# Mergen_Ground_Station_V2_0.net
KiCad netlist of a schematic drawn in EAGLE
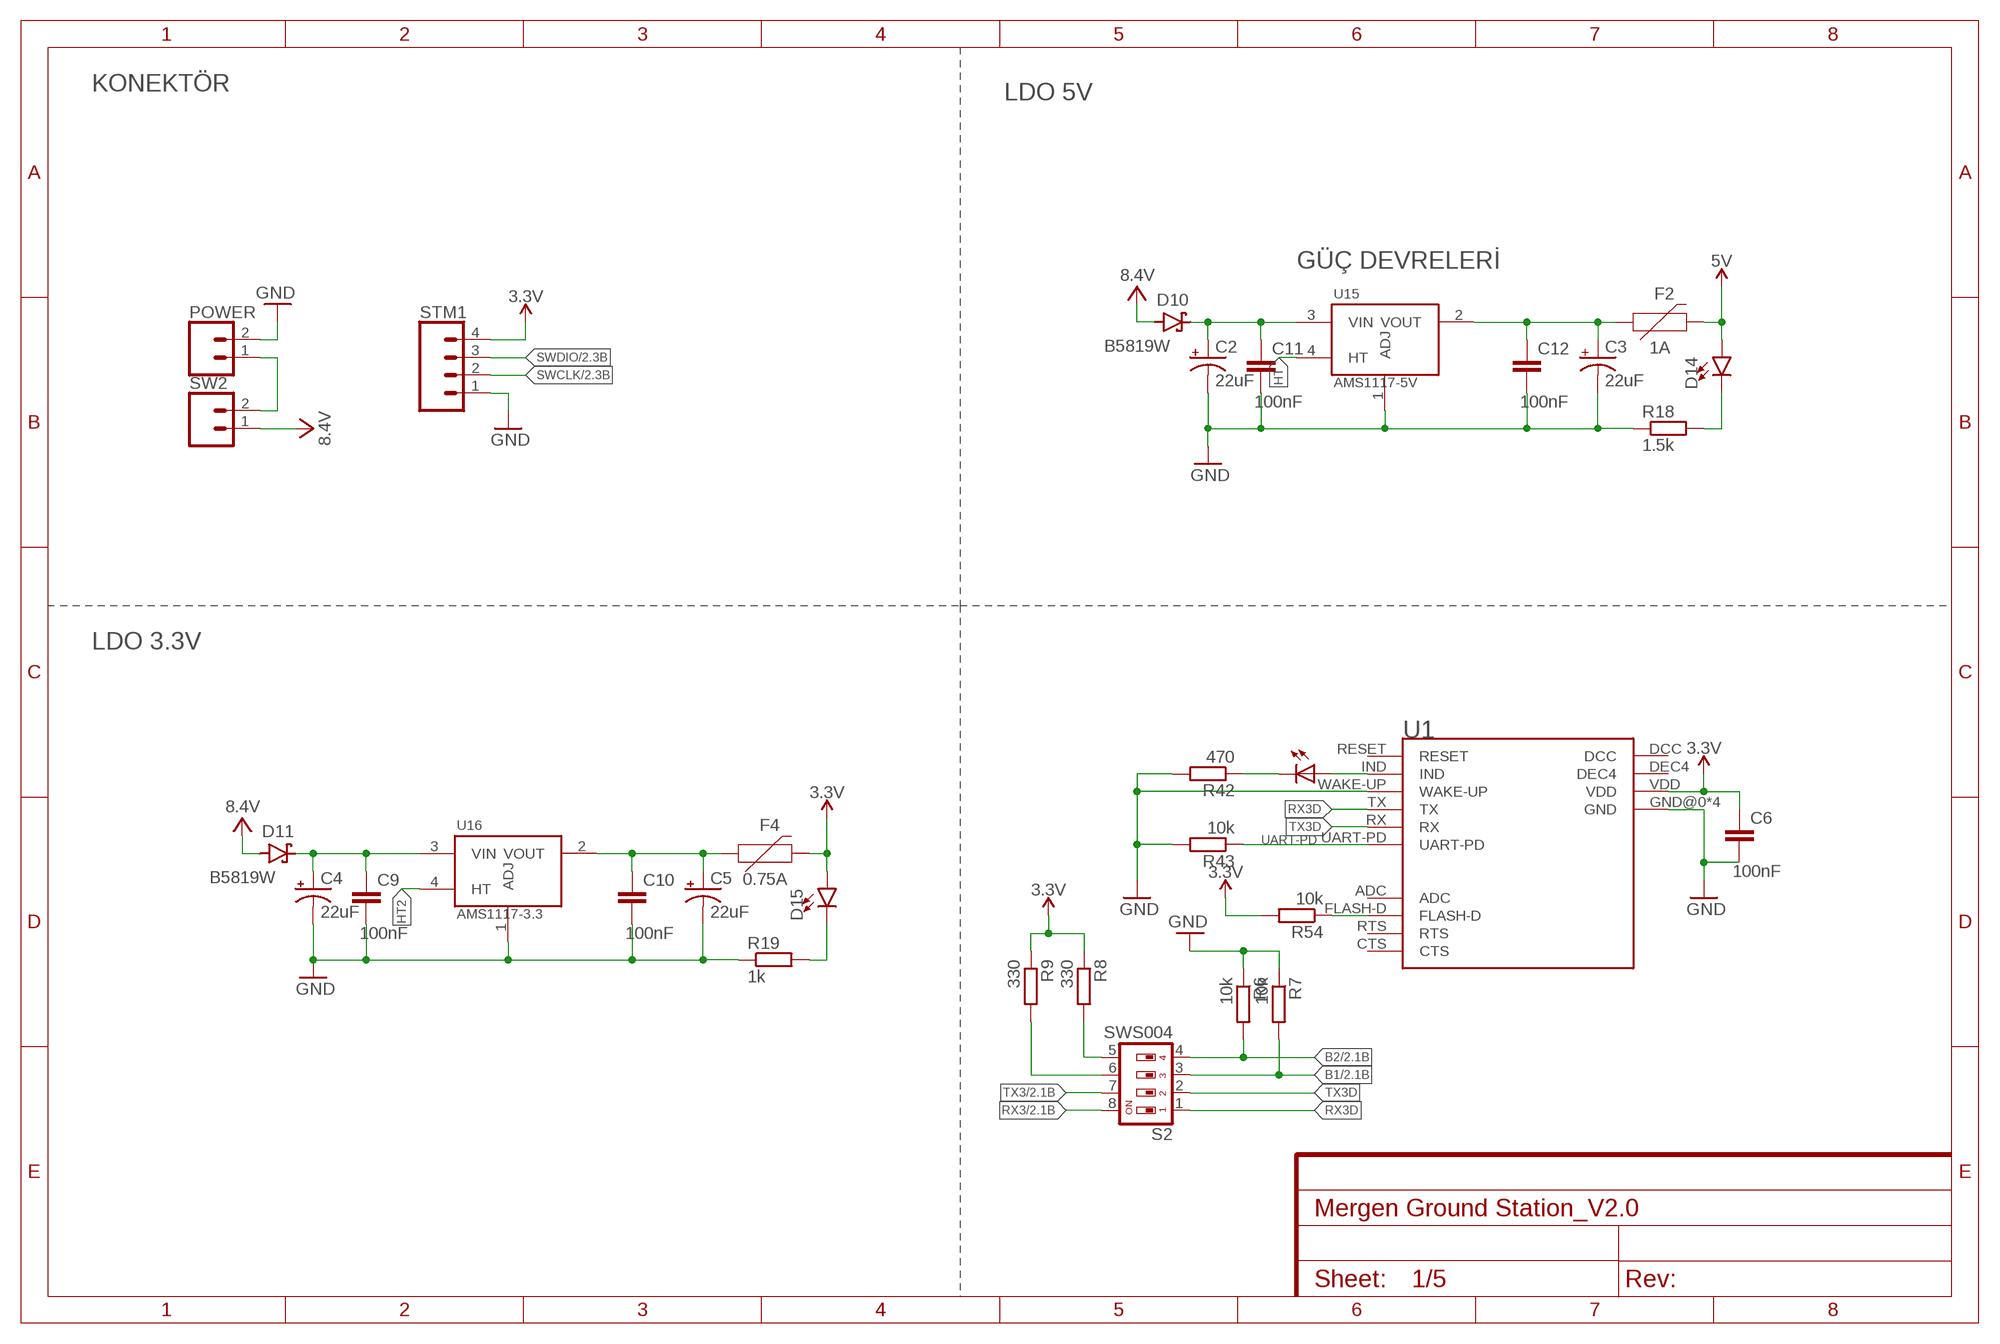
[diagram p0: schematic, sheet 1]
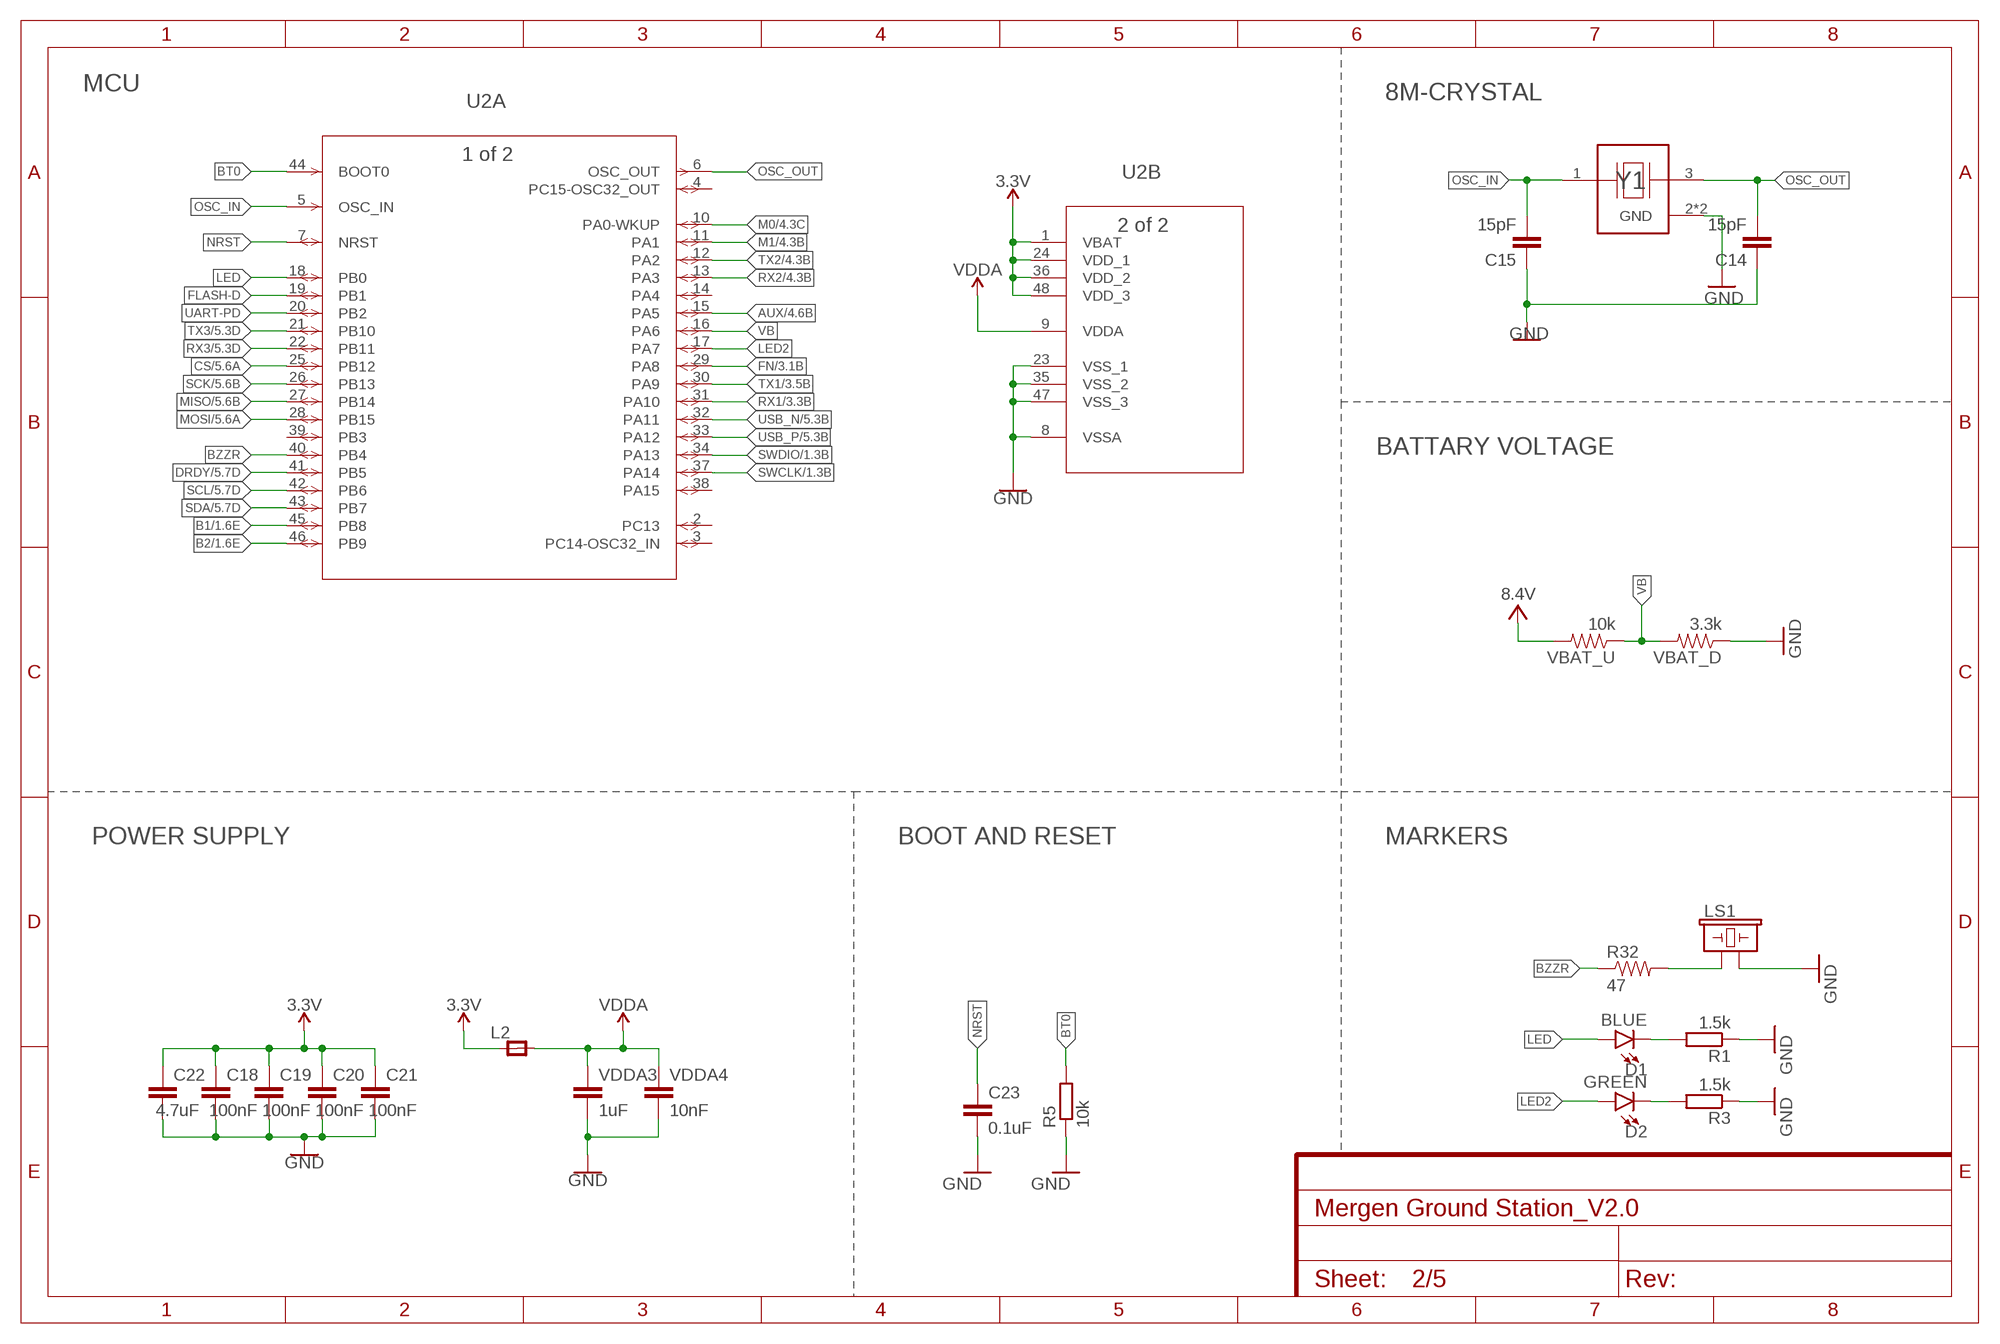
[diagram p1: schematic, sheet 2]
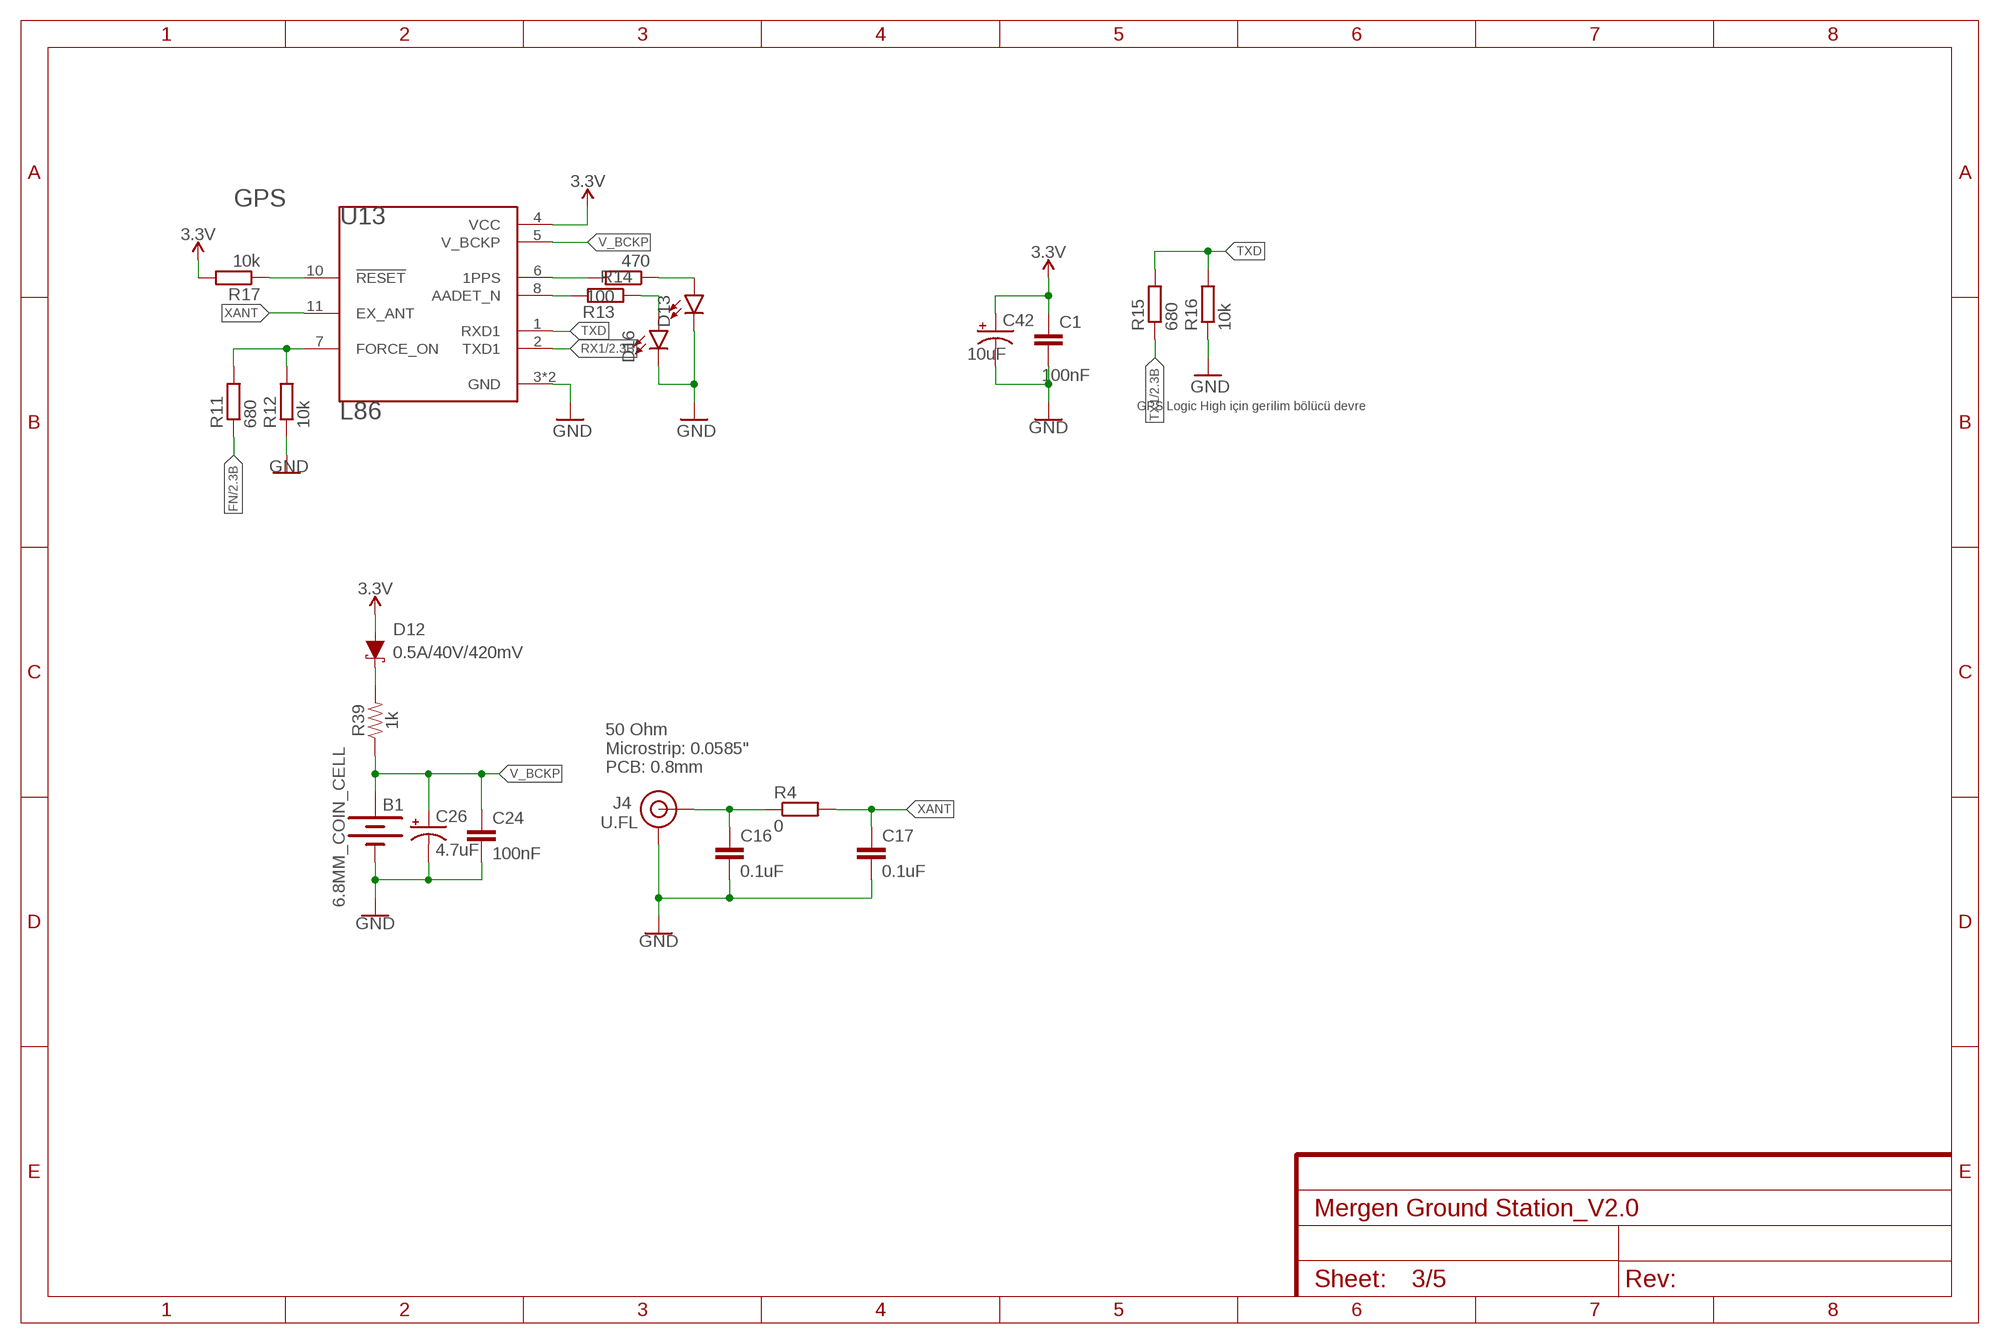
[diagram p2: schematic, sheet 3]
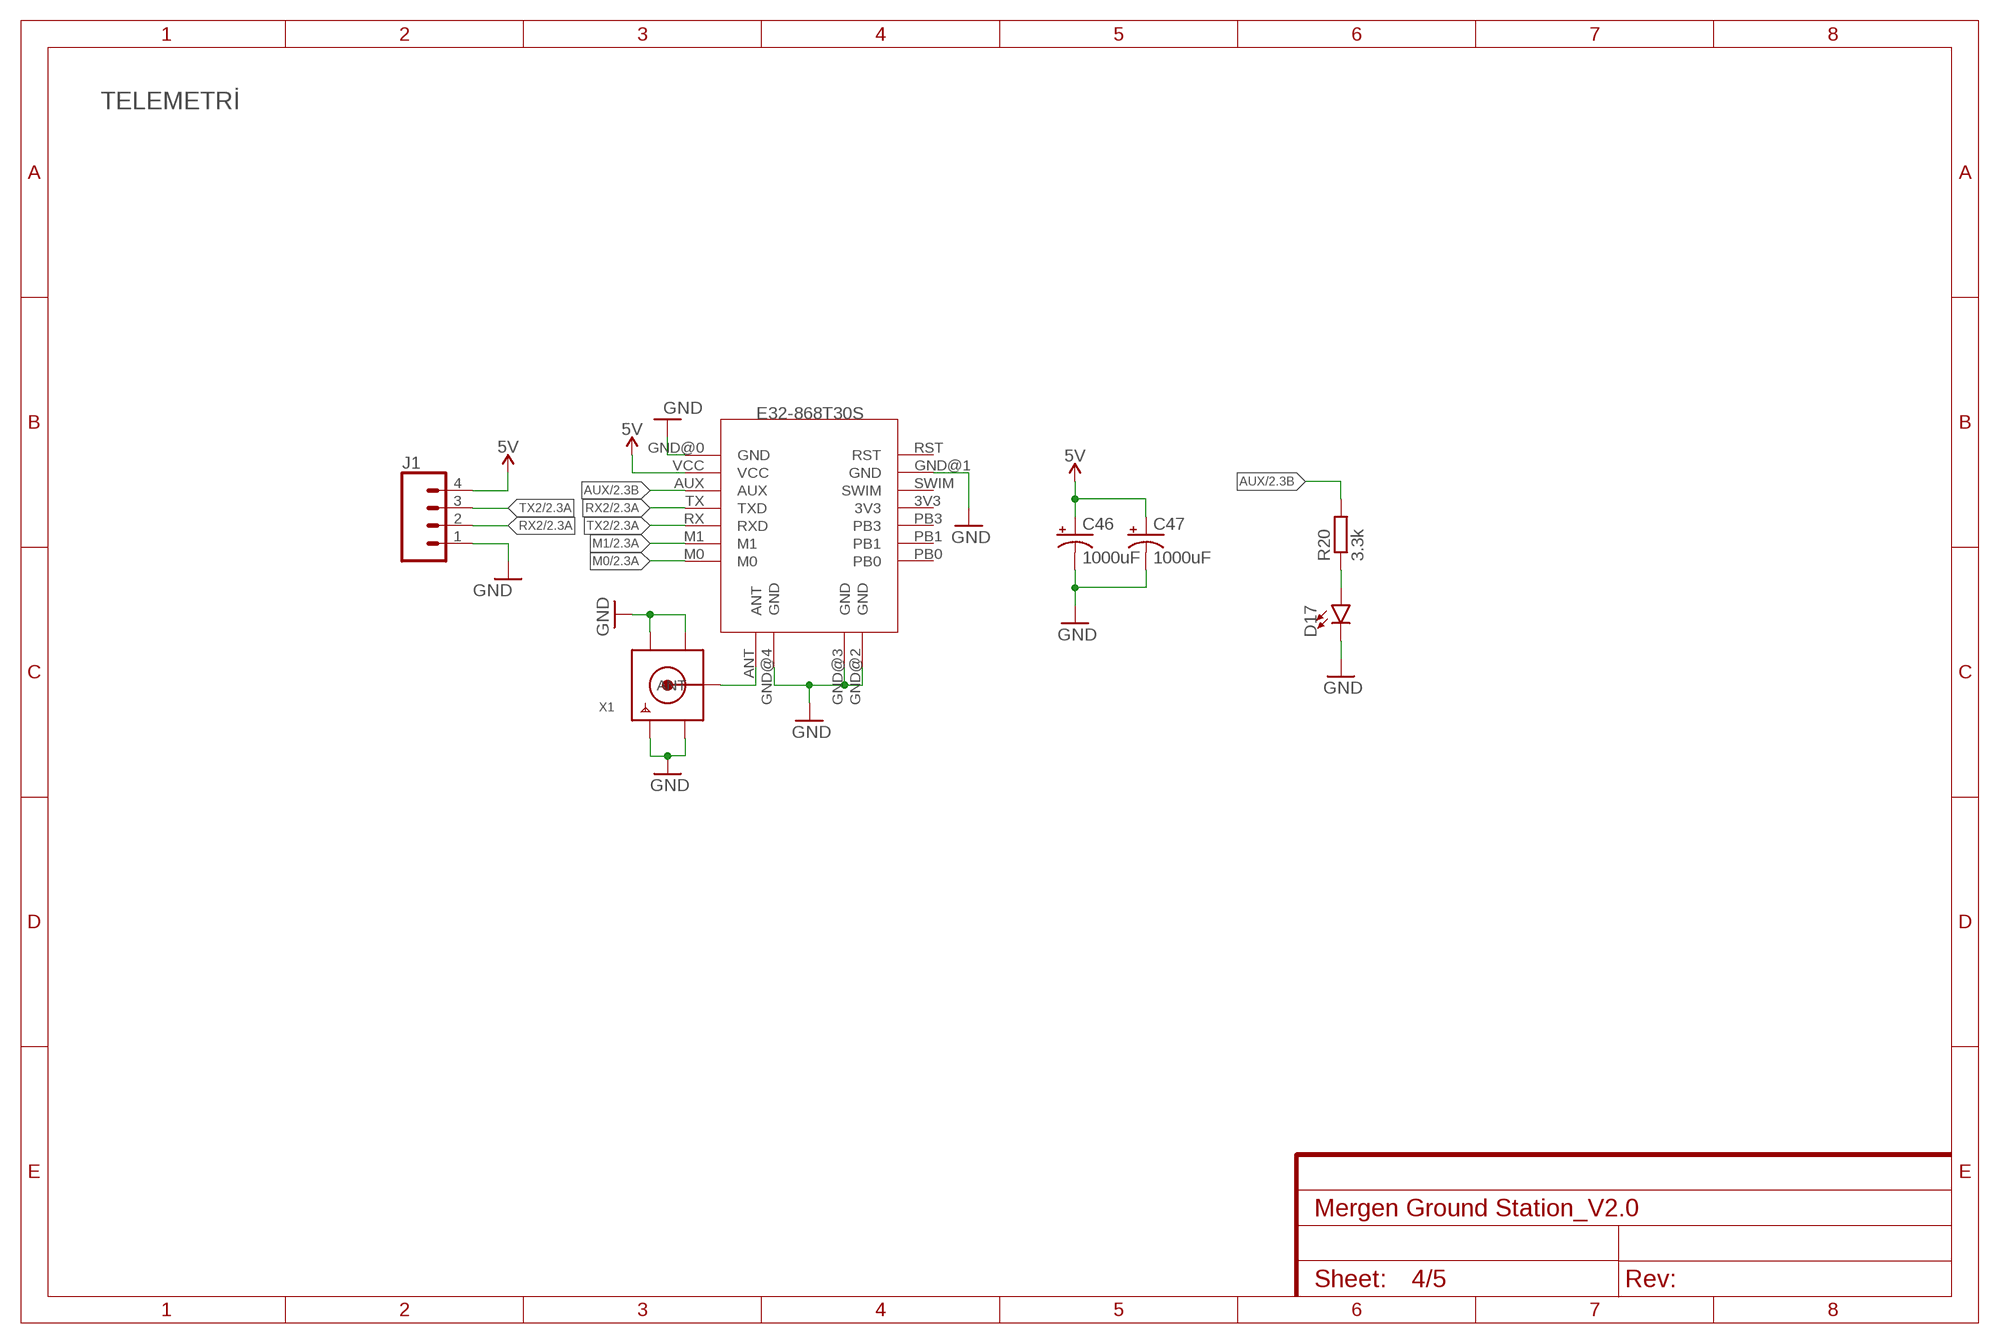
[diagram p3: schematic, sheet 4]
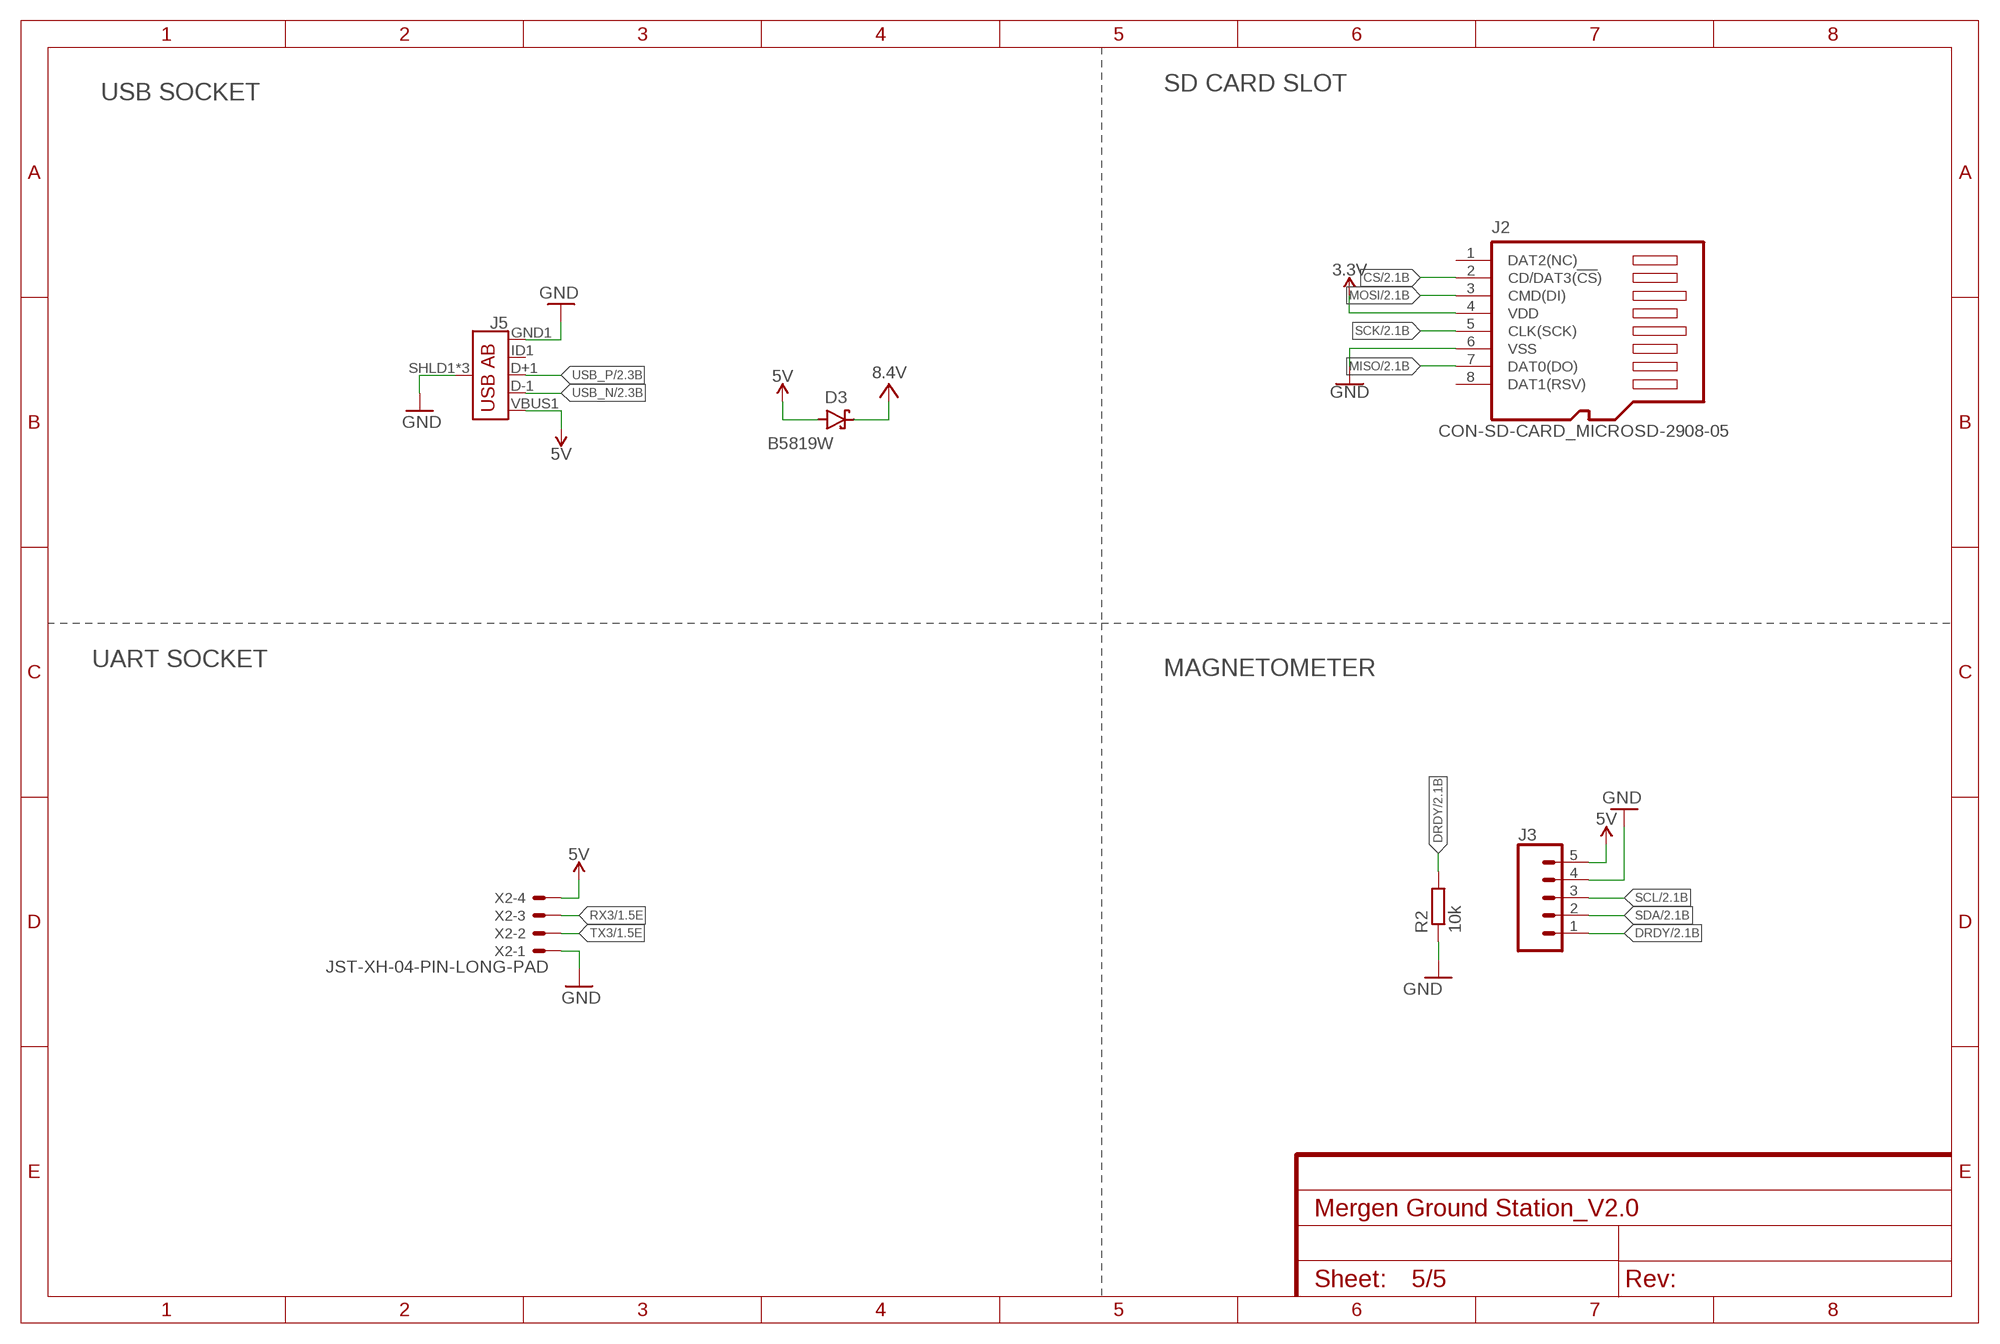
[diagram p4: schematic, sheet 5]

(export (version "E")
  (design (tool "Eeschema 10.0.6"))
  (components
    (comp (ref "B1")
      (value "6.8MM_COIN_CELL")
      (footprint "eagle-import:BATTCON-6.8MM")
      (libsource (lib "eagle-import") (part "BATTERY-6.8MM_SMD"))
    )
    (comp (ref "C1")
      (value "100nF")
      (footprint "eagle-import:C0603")
      (libsource (lib "eagle-import") (part "C-EUC0603"))
    )
    (comp (ref "C16")
      (value "0.1uF")
      (footprint "eagle-import:C0603")
      (libsource (lib "eagle-import") (part "C-EUC0603"))
    )
    (comp (ref "C17")
      (value "0.1uF")
      (footprint "eagle-import:C0603")
      (libsource (lib "eagle-import") (part "C-EUC0603"))
    )
    (comp (ref "C24")
      (value "100nF")
      (footprint "eagle-import:C0603")
      (libsource (lib "eagle-import") (part "C-EUC0603"))
    )
    (comp (ref "C26")
      (value "4.7uF")
      (footprint "eagle-import:A_3216-18R")
      (libsource (lib "eagle-import") (part "rcl_334_CPOL-USA/3216-18R"))
    )
    (comp (ref "C42")
      (value "10uF")
      (footprint "eagle-import:EIA3216")
      (libsource (lib "eagle-import") (part "10UF-POLAR-EIA3216-16V-10%(TANT)"))
    )
    (comp (ref "D12")
      (value "0.5A/40V/420mV")
      (footprint "eagle-import:SOD-323")
      (libsource (lib "eagle-import") (part "DIODE-SCHOTTKY-PMEG4005EJ"))
    )
    (comp (ref "D13")
      (value "LED0603")
      (footprint "eagle-import:LED-0603")
      (libsource (lib "eagle-import") (part "LED0603"))
    )
    (comp (ref "D16")
      (value "LED0603")
      (footprint "eagle-import:LED-0603")
      (libsource (lib "eagle-import") (part "LED0603"))
    )
    (comp (ref "J4")
      (value "U.FL")
      (footprint "eagle-import:U.FL")
      (libsource (lib "eagle-import") (part "U.FL2PIN"))
    )
    (comp (ref "R4")
      (value "0")
      (footprint "eagle-import:R0603")
      (libsource (lib "eagle-import") (part "rcl_334_R-EU_R0603"))
    )
    (comp (ref "R11")
      (value "680")
      (footprint "eagle-import:R0603")
      (libsource (lib "eagle-import") (part "rcl_334_R-EU_R0603"))
    )
    (comp (ref "R12")
      (value "10k")
      (footprint "eagle-import:R0603")
      (libsource (lib "eagle-import") (part "rcl_334_R-EU_R0603"))
    )
    (comp (ref "R13")
      (value "100")
      (footprint "eagle-import:R0603")
      (libsource (lib "eagle-import") (part "rcl_334_R-EU_R0603"))
    )
    (comp (ref "R14")
      (value "470")
      (footprint "eagle-import:R0603")
      (libsource (lib "eagle-import") (part "rcl_334_R-EU_R0603"))
    )
    (comp (ref "R15")
      (value "680")
      (footprint "eagle-import:R0603")
      (libsource (lib "eagle-import") (part "rcl_334_R-EU_R0603"))
    )
    (comp (ref "R16")
      (value "10k")
      (footprint "eagle-import:R0603")
      (libsource (lib "eagle-import") (part "rcl_334_R-EU_R0603"))
    )
    (comp (ref "R17")
      (value "10k")
      (footprint "eagle-import:R0603")
      (libsource (lib "eagle-import") (part "rcl_334_R-EU_R0603"))
    )
    (comp (ref "R39")
      (value "1k")
      (footprint "eagle-import:0603")
      (libsource (lib "eagle-import") (part "1KOHM-0603-1/10W-1%"))
    )
    (comp (ref "U13")
      (value "L86")
      (footprint "eagle-import:XCVR_L86")
      (fields (field (name "MF") "Quectel"))
      (libsource (lib "eagle-import") (part "L86"))
    )
    (comp (ref "C2")
      (value "22uF")
      (footprint "eagle-import:CT3528")
      (libsource (lib "eagle-import") (part "rcl_334_CPOL-USCT3528"))
    )
    (comp (ref "C3")
      (value "22uF")
      (footprint "eagle-import:CT3528")
      (libsource (lib "eagle-import") (part "rcl_334_CPOL-USCT3528"))
    )
    (comp (ref "C4")
      (value "22uF")
      (footprint "eagle-import:CT3528")
      (libsource (lib "eagle-import") (part "rcl_334_CPOL-USCT3528"))
    )
    (comp (ref "C5")
      (value "22uF")
      (footprint "eagle-import:CT3528")
      (libsource (lib "eagle-import") (part "rcl_334_CPOL-USCT3528"))
    )
    (comp (ref "C6")
      (value "100nF")
      (footprint "eagle-import:C0603")
      (libsource (lib "eagle-import") (part "C-EUC0603"))
    )
    (comp (ref "C9")
      (value "100nF")
      (footprint "eagle-import:C0603")
      (libsource (lib "eagle-import") (part "C-EUC0603"))
    )
    (comp (ref "C10")
      (value "100nF")
      (footprint "eagle-import:C0603")
      (libsource (lib "eagle-import") (part "C-EUC0603"))
    )
    (comp (ref "C11")
      (value "100nF")
      (footprint "eagle-import:C0603")
      (libsource (lib "eagle-import") (part "C-EUC0603"))
    )
    (comp (ref "C12")
      (value "100nF")
      (footprint "eagle-import:C0603")
      (libsource (lib "eagle-import") (part "C-EUC0603"))
    )
    (comp (ref "D10")
      (value "B5819W")
      (footprint "eagle-import:SODFL3718X115")
      (fields (field (name "MANUFACTURER") "ON Semiconductor") (field (name "MPN") "MBR0520LT1G"))
      (libsource (lib "eagle-import") (part "SCHOTTKY_DO-219MBR0520LT1G"))
    )
    (comp (ref "D11")
      (value "B5819W")
      (footprint "eagle-import:SODFL3718X115")
      (fields (field (name "MANUFACTURER") "ON Semiconductor") (field (name "MPN") "MBR0520LT1G"))
      (libsource (lib "eagle-import") (part "SCHOTTKY_DO-219MBR0520LT1G"))
    )
    (comp (ref "D14")
      (value "LED0603")
      (footprint "eagle-import:LED-0603")
      (libsource (lib "eagle-import") (part "LED0603"))
    )
    (comp (ref "D15")
      (value "LED0603")
      (footprint "eagle-import:LED-0603")
      (libsource (lib "eagle-import") (part "LED0603"))
    )
    (comp (ref "DRM3")
      (value "kirmizi")
      (footprint "eagle-import:CHIP-LED0805")
      (libsource (lib "eagle-import") (part "LEDCHIP-LED0805"))
    )
    (comp (ref "F2")
      (value "1A")
      (footprint "eagle-import:1206")
      (libsource (lib "eagle-import") (part "PPTC_HALF-AMP"))
    )
    (comp (ref "F4")
      (value "0.75A")
      (footprint "eagle-import:1206")
      (libsource (lib "eagle-import") (part "PPTC_HALF-AMP"))
    )
    (comp (ref "POWER")
      (value "CONN_023.5MM-NO_SILK")
      (footprint "eagle-import:SCREWTERMINAL-3.5MM-2-NS")
      (libsource (lib "eagle-import") (part "CONN_023.5MM-NO_SILK"))
    )
    (comp (ref "R6")
      (value "10k")
      (footprint "eagle-import:R0603")
      (libsource (lib "eagle-import") (part "R-EU_R0603"))
    )
    (comp (ref "R7")
      (value "10k")
      (footprint "eagle-import:R0603")
      (libsource (lib "eagle-import") (part "R-EU_R0603"))
    )
    (comp (ref "R8")
      (value "330")
      (footprint "eagle-import:R0603")
      (libsource (lib "eagle-import") (part "R-EU_R0603"))
    )
    (comp (ref "R9")
      (value "330")
      (footprint "eagle-import:R0603")
      (libsource (lib "eagle-import") (part "R-EU_R0603"))
    )
    (comp (ref "R18")
      (value "1.5k")
      (footprint "eagle-import:R0603")
      (libsource (lib "eagle-import") (part "rcl_334_R-EU_R0603"))
    )
    (comp (ref "R19")
      (value "1k")
      (footprint "eagle-import:R0603")
      (libsource (lib "eagle-import") (part "rcl_334_R-EU_R0603"))
    )
    (comp (ref "R42")
      (value "470")
      (footprint "eagle-import:R0603")
      (libsource (lib "eagle-import") (part "R-EU_R0603"))
    )
    (comp (ref "R43")
      (value "10k")
      (footprint "eagle-import:R0603")
      (libsource (lib "eagle-import") (part "R-EU_R0603"))
    )
    (comp (ref "R54")
      (value "10k")
      (footprint "eagle-import:R0603")
      (libsource (lib "eagle-import") (part "R-EU_R0603"))
    )
    (comp (ref "S2")
      (value "SWS004")
      (footprint "eagle-import:SMS-004")
      (libsource (lib "eagle-import") (part "SWS004"))
    )
    (comp (ref "STM1")
      (value "CONN_04")
      (footprint "eagle-import:1X04")
      (libsource (lib "eagle-import") (part "SparkFun-Connectors_513_CONN_04"))
    )
    (comp (ref "SW2")
      (value "CONN_023.5MM-NO_SILK")
      (footprint "eagle-import:SCREWTERMINAL-3.5MM-2-NS")
      (libsource (lib "eagle-import") (part "CONN_023.5MM-NO_SILK"))
    )
    (comp (ref "U1")
      (value "MDBT42T-AT")
      (footprint "eagle-import:MDBT42T-AT")
      (libsource (lib "eagle-import") (part "MDBT42T-AT"))
    )
    (comp (ref "U15")
      (value "AMS1117-5V")
      (footprint "eagle-import:SOT229P700X180-4N")
      (fields (field (name "MF") "Advanced Monolithic Systems") (field (name "MP") "AMS1117-3.3"))
      (libsource (lib "eagle-import") (part "AMS1117-3.3"))
    )
    (comp (ref "U16")
      (value "AMS1117-3.3")
      (footprint "eagle-import:SOT229P700X180-4N")
      (fields (field (name "MF") "Advanced Monolithic Systems"))
      (libsource (lib "eagle-import") (part "AMS1117-3.3"))
    )
    (comp (ref "D3")
      (value "B5819W")
      (footprint "eagle-import:SODFL3718X115")
      (fields (field (name "MANUFACTURER") "ON Semiconductor") (field (name "MPN") "MBR0520LT1G"))
      (libsource (lib "eagle-import") (part "SCHOTTKY_DO-219MBR0520LT1G"))
    )
    (comp (ref "J2")
      (value "CON-SD-CARD_MICROSD-2908-05")
      (footprint "eagle-import:CON-SD-CARD_2908-05")
      (libsource (lib "eagle-import") (part "CON-SD-CARD_MICROSD-2908-05"))
    )
    (comp (ref "J3")
      (value "CONN_05LOCK_LONGPADS")
      (footprint "eagle-import:1X05_LOCK_LONGPADS")
      (libsource (lib "eagle-import") (part "CONN_05LOCK_LONGPADS"))
    )
    (comp (ref "J5")
      (value "USB_AB_SMT")
      (footprint "eagle-import:USB-AB-MICRO-SMD")
      (libsource (lib "eagle-import") (part "USB_AB_SMT"))
    )
    (comp (ref "R2")
      (value "10k")
      (footprint "eagle-import:R0603")
      (libsource (lib "eagle-import") (part "rcl_334_R-EU_R0603"))
    )
    (comp (ref "X2")
      (value "JST-XH-04-PIN-LONG-PAD")
      (footprint "eagle-import:JST-XH-04-PACKAGE-LONG-PAD")
      (libsource (lib "eagle-import") (part "JST-XH-04-PIN-LONG-PAD"))
    )
    (comp (ref "C14")
      (value "15pF")
      (footprint "eagle-import:C0603")
      (libsource (lib "eagle-import") (part "C-EUC0603"))
    )
    (comp (ref "C15")
      (value "15pF")
      (footprint "eagle-import:C0603")
      (libsource (lib "eagle-import") (part "C-EUC0603"))
    )
    (comp (ref "C18")
      (value "100nF")
      (footprint "eagle-import:C0603")
      (libsource (lib "eagle-import") (part "C-EUC0603"))
    )
    (comp (ref "C19")
      (value "100nF")
      (footprint "eagle-import:C0603")
      (libsource (lib "eagle-import") (part "C-EUC0603"))
    )
    (comp (ref "C20")
      (value "100nF")
      (footprint "eagle-import:C0603")
      (libsource (lib "eagle-import") (part "C-EUC0603"))
    )
    (comp (ref "C21")
      (value "100nF")
      (footprint "eagle-import:C0603")
      (libsource (lib "eagle-import") (part "C-EUC0603"))
    )
    (comp (ref "C22")
      (value "4.7uF")
      (footprint "eagle-import:C0603")
      (libsource (lib "eagle-import") (part "C-EUC0603"))
    )
    (comp (ref "C23")
      (value "0.1uF")
      (footprint "eagle-import:C0603")
      (libsource (lib "eagle-import") (part "C-EUC0603"))
    )
    (comp (ref "D1")
      (value "BLUE")
      (footprint "eagle-import:LED-0603")
      (libsource (lib "eagle-import") (part "LED0603"))
    )
    (comp (ref "D2")
      (value "GREEN")
      (footprint "eagle-import:LED-0603")
      (libsource (lib "eagle-import") (part "LED0603"))
    )
    (comp (ref "L2")
      (value "RC-MASTER-SMD_FB_0805MP")
      (footprint "eagle-import:RC-MASTER-SMD_L0805MP")
      (libsource (lib "eagle-import") (part "RC-MASTER-SMD_FB_0805MP"))
    )
    (comp (ref "LS1")
      (value "BUZZER-PTH")
      (footprint "eagle-import:BUZZER-12MM")
      (libsource (lib "eagle-import") (part "BUZZER-PTH"))
    )
    (comp (ref "R1")
      (value "1.5k")
      (footprint "eagle-import:R0603")
      (libsource (lib "eagle-import") (part "rcl_334_R-EU_R0603"))
    )
    (comp (ref "R3")
      (value "1.5k")
      (footprint "eagle-import:R0603")
      (libsource (lib "eagle-import") (part "rcl_334_R-EU_R0603"))
    )
    (comp (ref "R5")
      (value "10k")
      (footprint "eagle-import:R0603")
      (libsource (lib "eagle-import") (part "rcl_334_R-EU_R0603"))
    )
    (comp (ref "R32")
      (value "47")
      (footprint "eagle-import:0603")
      (libsource (lib "eagle-import") (part "0OHM-0603-1/10W-5%"))
    )
    (comp (ref "U2")
      (value "STM32F103C8T6")
      (footprint "eagle-import:LQFP48-7X7MM")
      (fields (field (name "COPYRIGHT") "Copyright (C) 2018 Accelerated Designs. All rights reserved"))
      (libsource (lib "eagle-import") (part "STM32F103C8T6"))
    )
    (comp (ref "VBAT_D")
      (value "3.3k")
      (footprint "eagle-import:0603-RES")
      (libsource (lib "eagle-import") (part "2.0KOHM1/10W5%(0603)"))
    )
    (comp (ref "VBAT_U")
      (value "10k")
      (footprint "eagle-import:0603-RES")
      (libsource (lib "eagle-import") (part "2.0KOHM1/10W5%(0603)"))
    )
    (comp (ref "VDDA3")
      (value "1uF")
      (footprint "eagle-import:0603")
      (libsource (lib "eagle-import") (part "0.1UF-0603-25V-(+80/-20%)"))
    )
    (comp (ref "VDDA4")
      (value "10nF")
      (footprint "eagle-import:0603")
      (libsource (lib "eagle-import") (part "0.1UF-0603-25V-(+80/-20%)"))
    )
    (comp (ref "Y1")
      (value "ABMM2-8.000MHZ-E2-T")
      (footprint "eagle-import:XTAL_ABMM2-8.000MHZ-E2-T")
      (fields (field (name "MF") "Abracon"))
      (libsource (lib "eagle-import") (part "ABMM2-8.000MHZ-E2-T"))
    )
    (comp (ref "C46")
      (value "1000uF")
      (footprint "eagle-import:150CLZ-1010")
      (libsource (lib "eagle-import") (part "CPOL-US150CLZ-1010"))
    )
    (comp (ref "C47")
      (value "1000uF")
      (footprint "eagle-import:150CLZ-1010")
      (libsource (lib "eagle-import") (part "CPOL-US150CLZ-1010"))
    )
    (comp (ref "D17")
      (value "LED0603")
      (footprint "eagle-import:LED-0603")
      (libsource (lib "eagle-import") (part "LED0603"))
    )
    (comp (ref "J1")
      (value "CONN_04")
      (footprint "eagle-import:1X04")
      (libsource (lib "eagle-import") (part "CONN_04"))
    )
    (comp (ref "R20")
      (value "3.3k")
      (footprint "eagle-import:R0603")
      (libsource (lib "eagle-import") (part "rcl_334_R-EU_R0603"))
    )
    (comp (ref "U14")
      (value "E32-868T30S")
      (footprint "eagle-import:E32-868T30S")
      (libsource (lib "eagle-import") (part "E32-868T30S"))
    )
    (comp (ref "X1")
      (value "SMACONNECTOR")
      (footprint "eagle-import:SMA90_DIP")
      (libsource (lib "eagle-import") (part "SMACONNECTOR"))
    )
  )
  (nets
    (net (code "1") (name "3.3V") (class "Default")
      (node (ref "C1") (pin "1") (pinfunction "1_1") (pintype "passive"))
      (node (ref "C18") (pin "1") (pinfunction "1_1") (pintype "passive"))
      (node (ref "C19") (pin "1") (pinfunction "1_1") (pintype "passive"))
      (node (ref "C20") (pin "1") (pinfunction "1_1") (pintype "passive"))
      (node (ref "C21") (pin "1") (pinfunction "1_1") (pintype "passive"))
      (node (ref "C22") (pin "1") (pinfunction "1_1") (pintype "passive"))
      (node (ref "C42") (pin "+") (pinfunction "+_+") (pintype "passive"))
      (node (ref "C6") (pin "1") (pinfunction "1_1") (pintype "passive"))
      (node (ref "D12") (pin "A") (pinfunction "A_A") (pintype "passive"))
      (node (ref "D15") (pin "A") (pinfunction "A_A") (pintype "passive"))
      (node (ref "F4") (pin "2") (pinfunction "2_2") (pintype "bidirectional"))
      (node (ref "J2") (pin "4") (pinfunction "VDD_4") (pintype "bidirectional"))
      (node (ref "L2") (pin "1") (pinfunction "1_1") (pintype "passive"))
      (node (ref "R17") (pin "2") (pinfunction "2_2") (pintype "passive"))
      (node (ref "R54") (pin "2") (pinfunction "2_2") (pintype "passive"))
      (node (ref "R8") (pin "1") (pinfunction "1_1") (pintype "passive"))
      (node (ref "R9") (pin "1") (pinfunction "1_1") (pintype "passive"))
      (node (ref "STM1") (pin "4") (pinfunction "4_4") (pintype "passive"))
      (node (ref "U1") (pin "VDD") (pinfunction "VDD_VDD") (pintype "bidirectional"))
      (node (ref "U13") (pin "4") (pinfunction "VCC_4") (pintype "power_in"))
      (node (ref "U2") (pin "1") (pinfunction "VBAT_1") (pintype "power_in"))
      (node (ref "U2") (pin "24") (pinfunction "VDD_1_24") (pintype "power_in"))
      (node (ref "U2") (pin "36") (pinfunction "VDD_2_36") (pintype "power_in"))
      (node (ref "U2") (pin "48") (pinfunction "VDD_3_48") (pintype "power_in"))
    )
    (net (code "2") (name "5V") (class "Default")
      (node (ref "C46") (pin "+") (pinfunction "+_+") (pintype "passive"))
      (node (ref "C47") (pin "+") (pinfunction "+_+") (pintype "passive"))
      (node (ref "D14") (pin "A") (pinfunction "A_A") (pintype "passive"))
      (node (ref "D3") (pin "2") (pinfunction "A_2") (pintype "passive"))
      (node (ref "F2") (pin "2") (pinfunction "2_2") (pintype "bidirectional"))
      (node (ref "J1") (pin "4") (pinfunction "4_4") (pintype "passive"))
      (node (ref "J3") (pin "5") (pinfunction "5_5") (pintype "passive"))
      (node (ref "J5") (pin "VBUS1") (pinfunction "VBUS_VBUS1") (pintype "power_in"))
      (node (ref "U14") (pin "VCC") (pinfunction "VCC_VCC") (pintype "bidirectional"))
      (node (ref "X2") (pin "4") (pinfunction "S_4") (pintype "passive"))
    )
    (net (code "3") (name "AUX") (class "Default")
      (node (ref "R20") (pin "2") (pinfunction "2_2") (pintype "passive"))
      (node (ref "U14") (pin "AUX") (pinfunction "AUX_AUX") (pintype "bidirectional"))
      (node (ref "U2") (pin "15") (pinfunction "PA5_15") (pintype "bidirectional"))
    )
    (net (code "4") (name "B1") (class "Default")
      (node (ref "R7") (pin "2") (pinfunction "2_2") (pintype "passive"))
      (node (ref "S2") (pin "3") (pinfunction "3_3") (pintype "passive"))
      (node (ref "U2") (pin "45") (pinfunction "PB8_45") (pintype "bidirectional"))
    )
    (net (code "5") (name "B2") (class "Default")
      (node (ref "R6") (pin "2") (pinfunction "2_2") (pintype "passive"))
      (node (ref "S2") (pin "4") (pinfunction "4_4") (pintype "passive"))
      (node (ref "U2") (pin "46") (pinfunction "PB9_46") (pintype "bidirectional"))
    )
    (net (code "6") (name "BT0") (class "Default")
      (node (ref "R5") (pin "2") (pinfunction "2_2") (pintype "passive"))
      (node (ref "U2") (pin "44") (pinfunction "BOOT0_44") (pintype "input"))
    )
    (net (code "7") (name "BZZR") (class "Default")
      (node (ref "R32") (pin "1") (pinfunction "1_1") (pintype "passive"))
      (node (ref "U2") (pin "40") (pinfunction "PB4_40") (pintype "bidirectional"))
    )
    (net (code "8") (name "CS") (class "Default")
      (node (ref "J2") (pin "2") (pinfunction "CD/DAT3(~{CS})_2") (pintype "bidirectional"))
      (node (ref "U2") (pin "25") (pinfunction "PB12_25") (pintype "bidirectional"))
    )
    (net (code "9") (name "DRDY") (class "Default")
      (node (ref "J3") (pin "1") (pinfunction "1_1") (pintype "passive"))
      (node (ref "R2") (pin "2") (pinfunction "2_2") (pintype "passive"))
      (node (ref "U2") (pin "41") (pinfunction "PB5_41") (pintype "bidirectional"))
    )
    (net (code "10") (name "FLASH-D") (class "Default")
      (node (ref "R54") (pin "1") (pinfunction "1_1") (pintype "passive"))
      (node (ref "U1") (pin "FLASH-D") (pinfunction "FLASH-D_FLASH-D") (pintype "bidirectional"))
      (node (ref "U2") (pin "19") (pinfunction "PB1_19") (pintype "bidirectional"))
    )
    (net (code "11") (name "FN") (class "Default")
      (node (ref "R11") (pin "1") (pinfunction "1_1") (pintype "passive"))
      (node (ref "U2") (pin "29") (pinfunction "PA8_29") (pintype "bidirectional"))
    )
    (net (code "12") (name "GND") (class "Default")
      (node (ref "B1") (pin "-") (pinfunction "-_-") (pintype "power_in"))
      (node (ref "C1") (pin "2") (pinfunction "2_2") (pintype "passive"))
      (node (ref "C10") (pin "2") (pinfunction "2_2") (pintype "passive"))
      (node (ref "C11") (pin "2") (pinfunction "2_2") (pintype "passive"))
      (node (ref "C12") (pin "2") (pinfunction "2_2") (pintype "passive"))
      (node (ref "C14") (pin "1") (pinfunction "1_1") (pintype "passive"))
      (node (ref "C15") (pin "1") (pinfunction "1_1") (pintype "passive"))
      (node (ref "C16") (pin "2") (pinfunction "2_2") (pintype "passive"))
      (node (ref "C17") (pin "2") (pinfunction "2_2") (pintype "passive"))
      (node (ref "C18") (pin "2") (pinfunction "2_2") (pintype "passive"))
      (node (ref "C19") (pin "2") (pinfunction "2_2") (pintype "passive"))
      (node (ref "C2") (pin "-") (pinfunction "-_-") (pintype "passive"))
      (node (ref "C20") (pin "2") (pinfunction "2_2") (pintype "passive"))
      (node (ref "C21") (pin "2") (pinfunction "2_2") (pintype "passive"))
      (node (ref "C22") (pin "2") (pinfunction "2_2") (pintype "passive"))
      (node (ref "C23") (pin "2") (pinfunction "2_2") (pintype "passive"))
      (node (ref "C24") (pin "2") (pinfunction "2_2") (pintype "passive"))
      (node (ref "C26") (pin "-") (pinfunction "-_-") (pintype "passive"))
      (node (ref "C3") (pin "-") (pinfunction "-_-") (pintype "passive"))
      (node (ref "C4") (pin "-") (pinfunction "-_-") (pintype "passive"))
      (node (ref "C42") (pin "-") (pinfunction "-_-") (pintype "passive"))
      (node (ref "C46") (pin "-") (pinfunction "-_-") (pintype "passive"))
      (node (ref "C47") (pin "-") (pinfunction "-_-") (pintype "passive"))
      (node (ref "C5") (pin "-") (pinfunction "-_-") (pintype "passive"))
      (node (ref "C6") (pin "2") (pinfunction "2_2") (pintype "passive"))
      (node (ref "C9") (pin "2") (pinfunction "2_2") (pintype "passive"))
      (node (ref "D13") (pin "C") (pinfunction "C_C") (pintype "passive"))
      (node (ref "D16") (pin "C") (pinfunction "C_C") (pintype "passive"))
      (node (ref "D17") (pin "C") (pinfunction "C_C") (pintype "passive"))
      (node (ref "J1") (pin "1") (pinfunction "1_1") (pintype "passive"))
      (node (ref "J2") (pin "6") (pinfunction "VSS_6") (pintype "bidirectional"))
      (node (ref "J3") (pin "4") (pinfunction "4_4") (pintype "passive"))
      (node (ref "J4") (pin "1") (pinfunction "GND_1") (pintype "bidirectional"))
      (node (ref "J4") (pin "2") (pinfunction "GND_2") (pintype "bidirectional"))
      (node (ref "J5") (pin "GND1") (pinfunction "GND_GND1") (pintype "power_in"))
      (node (ref "J5") (pin "SHLD1") (pinfunction "SHIELD_SHLD1") (pintype "bidirectional"))
      (node (ref "J5") (pin "SHLD2") (pinfunction "SHIELD_SHLD2") (pintype "bidirectional"))
      (node (ref "J5") (pin "SHLD3") (pinfunction "SHIELD_SHLD3") (pintype "bidirectional"))
      (node (ref "LS1") (pin "-") (pinfunction "2_-") (pintype "passive"))
      (node (ref "POWER") (pin "2") (pinfunction "2_2") (pintype "passive"))
      (node (ref "R1") (pin "1") (pinfunction "1_1") (pintype "passive"))
      (node (ref "R12") (pin "1") (pinfunction "1_1") (pintype "passive"))
      (node (ref "R16") (pin "1") (pinfunction "1_1") (pintype "passive"))
      (node (ref "R18") (pin "1") (pinfunction "1_1") (pintype "passive"))
      (node (ref "R19") (pin "1") (pinfunction "1_1") (pintype "passive"))
      (node (ref "R2") (pin "1") (pinfunction "1_1") (pintype "passive"))
      (node (ref "R3") (pin "1") (pinfunction "1_1") (pintype "passive"))
      (node (ref "R42") (pin "2") (pinfunction "2_2") (pintype "passive"))
      (node (ref "R43") (pin "2") (pinfunction "2_2") (pintype "passive"))
      (node (ref "R5") (pin "1") (pinfunction "1_1") (pintype "passive"))
      (node (ref "R6") (pin "1") (pinfunction "1_1") (pintype "passive"))
      (node (ref "R7") (pin "1") (pinfunction "1_1") (pintype "passive"))
      (node (ref "STM1") (pin "1") (pinfunction "1_1") (pintype "passive"))
      (node (ref "U1") (pin "GND@0") (pinfunction "GND_GND@0") (pintype "bidirectional"))
      (node (ref "U1") (pin "GND@1") (pinfunction "GND_GND@1") (pintype "bidirectional"))
      (node (ref "U1") (pin "GND@2") (pinfunction "GND_GND@2") (pintype "bidirectional"))
      (node (ref "U1") (pin "GND@3") (pinfunction "GND_GND@3") (pintype "bidirectional"))
      (node (ref "U1") (pin "WAKE-UP") (pinfunction "WAKE-UP_WAKE-UP") (pintype "bidirectional"))
      (node (ref "U13") (pin "12") (pinfunction "GND_12") (pintype "passive"))
      (node (ref "U13") (pin "3") (pinfunction "GND_3") (pintype "passive"))
      (node (ref "U14") (pin "GND@0") (pinfunction "GND_GND@0") (pintype "bidirectional"))
      (node (ref "U14") (pin "GND@1") (pinfunction "GND_GND@1") (pintype "bidirectional"))
      (node (ref "U14") (pin "GND@2") (pinfunction "GND_GND@2") (pintype "bidirectional"))
      (node (ref "U14") (pin "GND@3") (pinfunction "GND_GND@3") (pintype "bidirectional"))
      (node (ref "U14") (pin "GND@4") (pinfunction "GND_GND@4") (pintype "bidirectional"))
      (node (ref "U15") (pin "1") (pinfunction "ADJ_1") (pintype "power_in"))
      (node (ref "U16") (pin "1") (pinfunction "ADJ_1") (pintype "power_in"))
      (node (ref "U2") (pin "23") (pinfunction "VSS_1_23") (pintype "power_in"))
      (node (ref "U2") (pin "35") (pinfunction "VSS_2_35") (pintype "power_in"))
      (node (ref "U2") (pin "47") (pinfunction "VSS_3_47") (pintype "power_in"))
      (node (ref "U2") (pin "8") (pinfunction "VSSA_8") (pintype "power_in"))
      (node (ref "VBAT_D") (pin "1") (pinfunction "1_1") (pintype "passive"))
      (node (ref "VDDA3") (pin "2") (pinfunction "2_2") (pintype "passive"))
      (node (ref "VDDA4") (pin "2") (pinfunction "2_2") (pintype "passive"))
      (node (ref "X1") (pin "GND1") (pinfunction "GND1_GND1") (pintype "power_in"))
      (node (ref "X1") (pin "GND2") (pinfunction "GND2_GND2") (pintype "power_in"))
      (node (ref "X1") (pin "GND3") (pinfunction "GND3_GND3") (pintype "power_in"))
      (node (ref "X1") (pin "GND4") (pinfunction "GND4_GND4") (pintype "power_in"))
      (node (ref "X2") (pin "1") (pinfunction "S_1") (pintype "passive"))
      (node (ref "Y1") (pin "2") (pinfunction "GND_2") (pintype "power_in"))
      (node (ref "Y1") (pin "4") (pinfunction "GND_4") (pintype "power_in"))
    )
    (net (code "13") (name "HT") (class "Default")
      (node (ref "U15") (pin "4") (pinfunction "HT_4") (pintype "bidirectional"))
    )
    (net (code "14") (name "HT2") (class "Default")
      (node (ref "U16") (pin "4") (pinfunction "HT_4") (pintype "bidirectional"))
    )
    (net (code "15") (name "LED") (class "Default")
      (node (ref "D1") (pin "A") (pinfunction "A_A") (pintype "passive"))
      (node (ref "U2") (pin "18") (pinfunction "PB0_18") (pintype "bidirectional"))
    )
    (net (code "16") (name "LED2") (class "Default")
      (node (ref "D2") (pin "A") (pinfunction "A_A") (pintype "passive"))
      (node (ref "U2") (pin "17") (pinfunction "PA7_17") (pintype "bidirectional"))
    )
    (net (code "17") (name "M0") (class "Default")
      (node (ref "U14") (pin "M0") (pinfunction "M0_M0") (pintype "bidirectional"))
      (node (ref "U2") (pin "10") (pinfunction "PA0-WKUP_10") (pintype "bidirectional"))
    )
    (net (code "18") (name "M1") (class "Default")
      (node (ref "U14") (pin "M1") (pinfunction "M1_M1") (pintype "bidirectional"))
      (node (ref "U2") (pin "11") (pinfunction "PA1_11") (pintype "bidirectional"))
    )
    (net (code "19") (name "MISO") (class "Default")
      (node (ref "J2") (pin "7") (pinfunction "DAT0(DO)_7") (pintype "bidirectional"))
      (node (ref "U2") (pin "27") (pinfunction "PB14_27") (pintype "bidirectional"))
    )
    (net (code "20") (name "MOSI") (class "Default")
      (node (ref "J2") (pin "3") (pinfunction "CMD(DI)_3") (pintype "bidirectional"))
      (node (ref "U2") (pin "28") (pinfunction "PB15_28") (pintype "bidirectional"))
    )
    (net (code "21") (name "NRST") (class "Default")
      (node (ref "C23") (pin "1") (pinfunction "1_1") (pintype "passive"))
      (node (ref "U2") (pin "7") (pinfunction "NRST_7") (pintype "bidirectional"))
    )
    (net (code "22") (name "Net-(D1-PadC)") (class "Default")
      (node (ref "D1") (pin "C") (pinfunction "C_C") (pintype "passive"))
      (node (ref "R1") (pin "2") (pinfunction "2_2") (pintype "passive"))
    )
    (net (code "23") (name "Net-(D2-PadC)") (class "Default")
      (node (ref "D2") (pin "C") (pinfunction "C_C") (pintype "passive"))
      (node (ref "R3") (pin "2") (pinfunction "2_2") (pintype "passive"))
    )
    (net (code "24") (name "Net-(D10-C)") (class "Default")
      (node (ref "C11") (pin "1") (pinfunction "1_1") (pintype "passive"))
      (node (ref "C2") (pin "+") (pinfunction "+_+") (pintype "passive"))
      (node (ref "D10") (pin "1") (pinfunction "C_1") (pintype "passive"))
      (node (ref "U15") (pin "3") (pinfunction "VIN_3") (pintype "input"))
    )
    (net (code "25") (name "Net-(D11-C)") (class "Default")
      (node (ref "C4") (pin "+") (pinfunction "+_+") (pintype "passive"))
      (node (ref "C9") (pin "1") (pinfunction "1_1") (pintype "passive"))
      (node (ref "D11") (pin "1") (pinfunction "C_1") (pintype "passive"))
      (node (ref "U16") (pin "3") (pinfunction "VIN_3") (pintype "input"))
    )
    (net (code "26") (name "Net-(D12-PadC)") (class "Default")
      (node (ref "D12") (pin "C") (pinfunction "C_C") (pintype "passive"))
      (node (ref "R39") (pin "2") (pinfunction "2_2") (pintype "passive"))
    )
    (net (code "27") (name "Net-(D13-PadA)") (class "Default")
      (node (ref "D13") (pin "A") (pinfunction "A_A") (pintype "passive"))
      (node (ref "R14") (pin "1") (pinfunction "1_1") (pintype "passive"))
    )
    (net (code "28") (name "Net-(D14-PadC)") (class "Default")
      (node (ref "D14") (pin "C") (pinfunction "C_C") (pintype "passive"))
      (node (ref "R18") (pin "2") (pinfunction "2_2") (pintype "passive"))
    )
    (net (code "29") (name "Net-(D15-PadC)") (class "Default")
      (node (ref "D15") (pin "C") (pinfunction "C_C") (pintype "passive"))
      (node (ref "R19") (pin "2") (pinfunction "2_2") (pintype "passive"))
    )
    (net (code "30") (name "Net-(D16-PadA)") (class "Default")
      (node (ref "D16") (pin "A") (pinfunction "A_A") (pintype "passive"))
      (node (ref "R13") (pin "1") (pinfunction "1_1") (pintype "passive"))
    )
    (net (code "31") (name "Net-(D17-PadA)") (class "Default")
      (node (ref "D17") (pin "A") (pinfunction "A_A") (pintype "passive"))
      (node (ref "R20") (pin "1") (pinfunction "1_1") (pintype "passive"))
    )
    (net (code "32") (name "Net-(DRM3-PadA)") (class "Default")
      (node (ref "DRM3") (pin "A") (pinfunction "A_A") (pintype "passive"))
      (node (ref "U1") (pin "IND") (pinfunction "IND_IND") (pintype "bidirectional"))
    )
    (net (code "33") (name "Net-(DRM3-PadC)") (class "Default")
      (node (ref "DRM3") (pin "C") (pinfunction "C_C") (pintype "passive"))
      (node (ref "R42") (pin "1") (pinfunction "1_1") (pintype "passive"))
    )
    (net (code "34") (name "Net-(J4-SIGNAL)") (class "Default")
      (node (ref "C16") (pin "1") (pinfunction "1_1") (pintype "passive"))
      (node (ref "J4") (pin "FEED") (pinfunction "SIGNAL_FEED") (pintype "bidirectional"))
      (node (ref "R4") (pin "1") (pinfunction "1_1") (pintype "passive"))
    )
    (net (code "35") (name "Net-(LS1-1)") (class "Default")
      (node (ref "LS1") (pin "+") (pinfunction "1_+") (pintype "passive"))
      (node (ref "R32") (pin "2") (pinfunction "2_2") (pintype "passive"))
    )
    (net (code "36") (name "Net-(POWER-Pad1)") (class "Default")
      (node (ref "POWER") (pin "1") (pinfunction "1_1") (pintype "passive"))
      (node (ref "SW2") (pin "2") (pinfunction "2_2") (pintype "passive"))
    )
    (net (code "37") (name "Net-(R8-Pad2)") (class "Default")
      (node (ref "R8") (pin "2") (pinfunction "2_2") (pintype "passive"))
      (node (ref "S2") (pin "5") (pinfunction "5_5") (pintype "passive"))
    )
    (net (code "38") (name "Net-(R9-Pad2)") (class "Default")
      (node (ref "R9") (pin "2") (pinfunction "2_2") (pintype "passive"))
      (node (ref "S2") (pin "6") (pinfunction "6_6") (pintype "passive"))
    )
    (net (code "39") (name "Net-(U13-1PPS)") (class "Default")
      (node (ref "R14") (pin "2") (pinfunction "2_2") (pintype "passive"))
      (node (ref "U13") (pin "6") (pinfunction "1PPS_6") (pintype "output"))
    )
    (net (code "40") (name "Net-(U13-AADET_N)") (class "Default")
      (node (ref "R13") (pin "2") (pinfunction "2_2") (pintype "passive"))
      (node (ref "U13") (pin "8") (pinfunction "AADET_N_8") (pintype "output"))
    )
    (net (code "41") (name "Net-(U13-FORCE_ON)") (class "Default")
      (node (ref "R11") (pin "2") (pinfunction "2_2") (pintype "passive"))
      (node (ref "R12") (pin "2") (pinfunction "2_2") (pintype "passive"))
      (node (ref "U13") (pin "7") (pinfunction "FORCE_ON_7") (pintype "input"))
    )
    (net (code "42") (name "Net-(U13-~{RESET})") (class "Default")
      (node (ref "R17") (pin "1") (pinfunction "1_1") (pintype "passive"))
      (node (ref "U13") (pin "10") (pinfunction "~{RESET}_10") (pintype "input"))
    )
    (net (code "43") (name "Net-(U15-VOUT)") (class "Default")
      (node (ref "C12") (pin "1") (pinfunction "1_1") (pintype "passive"))
      (node (ref "C3") (pin "+") (pinfunction "+_+") (pintype "passive"))
      (node (ref "F2") (pin "1") (pinfunction "1_1") (pintype "bidirectional"))
      (node (ref "U15") (pin "2") (pinfunction "VOUT_2") (pintype "output"))
    )
    (net (code "44") (name "Net-(U16-VOUT)") (class "Default")
      (node (ref "C10") (pin "1") (pinfunction "1_1") (pintype "passive"))
      (node (ref "C5") (pin "+") (pinfunction "+_+") (pintype "passive"))
      (node (ref "F4") (pin "1") (pinfunction "1_1") (pintype "bidirectional"))
      (node (ref "U16") (pin "2") (pinfunction "VOUT_2") (pintype "output"))
    )
    (net (code "45") (name "Net-(X1-ANT)") (class "Default")
      (node (ref "U14") (pin "ANT") (pinfunction "ANT_ANT") (pintype "bidirectional"))
      (node (ref "X1") (pin "ANTENNA") (pinfunction "ANT_ANTENNA") (pintype "bidirectional"))
    )
    (net (code "46") (name "OSC_IN") (class "Default")
      (node (ref "C15") (pin "2") (pinfunction "2_2") (pintype "passive"))
      (node (ref "U2") (pin "5") (pinfunction "OSC_IN_5") (pintype "input"))
      (node (ref "Y1") (pin "1") (pinfunction "1_1") (pintype "passive"))
    )
    (net (code "47") (name "OSC_OUT") (class "Default")
      (node (ref "C14") (pin "2") (pinfunction "2_2") (pintype "passive"))
      (node (ref "U2") (pin "6") (pinfunction "OSC_OUT_6") (pintype "output"))
      (node (ref "Y1") (pin "3") (pinfunction "3_3") (pintype "passive"))
    )
    (net (code "48") (name "RX1") (class "Default")
      (node (ref "U13") (pin "2") (pinfunction "TXD1_2") (pintype "output"))
      (node (ref "U2") (pin "31") (pinfunction "PA10_31") (pintype "bidirectional"))
    )
    (net (code "49") (name "RX2") (class "Default")
      (node (ref "J1") (pin "2") (pinfunction "2_2") (pintype "passive"))
      (node (ref "U14") (pin "TX") (pinfunction "TXD_TX") (pintype "bidirectional"))
      (node (ref "U2") (pin "13") (pinfunction "PA3_13") (pintype "bidirectional"))
    )
    (net (code "50") (name "RX3") (class "Default")
      (node (ref "S2") (pin "8") (pinfunction "8_8") (pintype "passive"))
      (node (ref "U2") (pin "22") (pinfunction "PB11_22") (pintype "bidirectional"))
      (node (ref "X2") (pin "3") (pinfunction "S_3") (pintype "passive"))
    )
    (net (code "51") (name "RX3D") (class "Default")
      (node (ref "S2") (pin "1") (pinfunction "1_1") (pintype "passive"))
      (node (ref "U1") (pin "TX") (pinfunction "TX_TX") (pintype "bidirectional"))
    )
    (net (code "52") (name "SCK") (class "Default")
      (node (ref "J2") (pin "5") (pinfunction "CLK(SCK)_5") (pintype "bidirectional"))
      (node (ref "U2") (pin "26") (pinfunction "PB13_26") (pintype "bidirectional"))
    )
    (net (code "53") (name "SCL") (class "Default")
      (node (ref "J3") (pin "3") (pinfunction "3_3") (pintype "passive"))
      (node (ref "U2") (pin "42") (pinfunction "PB6_42") (pintype "bidirectional"))
    )
    (net (code "54") (name "SDA") (class "Default")
      (node (ref "J3") (pin "2") (pinfunction "2_2") (pintype "passive"))
      (node (ref "U2") (pin "43") (pinfunction "PB7_43") (pintype "bidirectional"))
    )
    (net (code "55") (name "SWCLK") (class "Default")
      (node (ref "STM1") (pin "2") (pinfunction "2_2") (pintype "passive"))
      (node (ref "U2") (pin "37") (pinfunction "PA14_37") (pintype "bidirectional"))
    )
    (net (code "56") (name "SWDIO") (class "Default")
      (node (ref "STM1") (pin "3") (pinfunction "3_3") (pintype "passive"))
      (node (ref "U2") (pin "34") (pinfunction "PA13_34") (pintype "bidirectional"))
    )
    (net (code "57") (name "TX1") (class "Default")
      (node (ref "R15") (pin "1") (pinfunction "1_1") (pintype "passive"))
      (node (ref "U2") (pin "30") (pinfunction "PA9_30") (pintype "bidirectional"))
    )
    (net (code "58") (name "TX2") (class "Default")
      (node (ref "J1") (pin "3") (pinfunction "3_3") (pintype "passive"))
      (node (ref "U14") (pin "RX") (pinfunction "RXD_RX") (pintype "bidirectional"))
      (node (ref "U2") (pin "12") (pinfunction "PA2_12") (pintype "bidirectional"))
    )
    (net (code "59") (name "TX3") (class "Default")
      (node (ref "S2") (pin "7") (pinfunction "7_7") (pintype "passive"))
      (node (ref "U2") (pin "21") (pinfunction "PB10_21") (pintype "bidirectional"))
      (node (ref "X2") (pin "2") (pinfunction "S_2") (pintype "passive"))
    )
    (net (code "60") (name "TX3D") (class "Default")
      (node (ref "S2") (pin "2") (pinfunction "2_2") (pintype "passive"))
      (node (ref "U1") (pin "RX") (pinfunction "RX_RX") (pintype "bidirectional"))
    )
    (net (code "61") (name "TXD") (class "Default")
      (node (ref "R15") (pin "2") (pinfunction "2_2") (pintype "passive"))
      (node (ref "R16") (pin "2") (pinfunction "2_2") (pintype "passive"))
      (node (ref "U13") (pin "1") (pinfunction "RXD1_1") (pintype "input"))
    )
    (net (code "62") (name "UART-PD") (class "Default")
      (node (ref "R43") (pin "1") (pinfunction "1_1") (pintype "passive"))
      (node (ref "U1") (pin "UART-PD") (pinfunction "UART-PD_UART-PD") (pintype "bidirectional"))
      (node (ref "U2") (pin "20") (pinfunction "PB2_20") (pintype "bidirectional"))
    )
    (net (code "63") (name "USB_N") (class "Default")
      (node (ref "J5") (pin "D-1") (pinfunction "D-_D-1") (pintype "bidirectional"))
      (node (ref "U2") (pin "32") (pinfunction "PA11_32") (pintype "bidirectional"))
    )
    (net (code "64") (name "USB_P") (class "Default")
      (node (ref "J5") (pin "D+1") (pinfunction "D+_D+1") (pintype "bidirectional"))
      (node (ref "U2") (pin "33") (pinfunction "PA12_33") (pintype "bidirectional"))
    )
    (net (code "65") (name "VB") (class "Default")
      (node (ref "U2") (pin "16") (pinfunction "PA6_16") (pintype "bidirectional"))
      (node (ref "VBAT_D") (pin "2") (pinfunction "2_2") (pintype "passive"))
      (node (ref "VBAT_U") (pin "1") (pinfunction "1_1") (pintype "passive"))
    )
    (net (code "66") (name "VCC") (class "Default")
      (node (ref "D10") (pin "2") (pinfunction "A_2") (pintype "passive"))
      (node (ref "D11") (pin "2") (pinfunction "A_2") (pintype "passive"))
      (node (ref "D3") (pin "1") (pinfunction "C_1") (pintype "passive"))
      (node (ref "SW2") (pin "1") (pinfunction "1_1") (pintype "passive"))
      (node (ref "VBAT_U") (pin "2") (pinfunction "2_2") (pintype "passive"))
    )
    (net (code "67") (name "VDDA") (class "Default")
      (node (ref "L2") (pin "2") (pinfunction "2_2") (pintype "passive"))
      (node (ref "U2") (pin "9") (pinfunction "VDDA_9") (pintype "power_in"))
      (node (ref "VDDA3") (pin "1") (pinfunction "1_1") (pintype "passive"))
      (node (ref "VDDA4") (pin "1") (pinfunction "1_1") (pintype "passive"))
    )
    (net (code "68") (name "V_BCKP") (class "Default")
      (node (ref "B1") (pin "+") (pinfunction "+_+") (pintype "power_in"))
      (node (ref "C24") (pin "1") (pinfunction "1_1") (pintype "passive"))
      (node (ref "C26") (pin "+") (pinfunction "+_+") (pintype "passive"))
      (node (ref "R39") (pin "1") (pinfunction "1_1") (pintype "passive"))
      (node (ref "U13") (pin "5") (pinfunction "V_BCKP_5") (pintype "power_in"))
    )
    (net (code "69") (name "XANT") (class "Default")
      (node (ref "C17") (pin "1") (pinfunction "1_1") (pintype "passive"))
      (node (ref "R4") (pin "2") (pinfunction "2_2") (pintype "passive"))
      (node (ref "U13") (pin "11") (pinfunction "EX_ANT_11") (pintype "input"))
    )
    (net (code "70") (name "unconnected-(J2B-DAT1(RSV)-Pad8)") (class "Default")
      (node (ref "J2") (pin "8") (pinfunction "DAT1(RSV)_8") (pintype "bidirectional"))
    )
    (net (code "71") (name "unconnected-(J2B-DAT2(NC)-Pad1)") (class "Default")
      (node (ref "J2") (pin "1") (pinfunction "DAT2(NC)_1") (pintype "bidirectional"))
    )
    (net (code "72") (name "unconnected-(J5-USBID-PadID1)") (class "Default")
      (node (ref "J5") (pin "ID1") (pinfunction "USBID_ID1") (pintype "bidirectional"))
    )
    (net (code "73") (name "unconnected-(U1-PadADC)") (class "Default")
      (node (ref "U1") (pin "ADC") (pinfunction "ADC_ADC") (pintype "bidirectional"))
    )
    (net (code "74") (name "unconnected-(U1-PadCTS)") (class "Default")
      (node (ref "U1") (pin "CTS") (pinfunction "CTS_CTS") (pintype "bidirectional"))
    )
    (net (code "75") (name "unconnected-(U1-PadDCC)") (class "Default")
      (node (ref "U1") (pin "DCC") (pinfunction "DCC_DCC") (pintype "bidirectional"))
    )
    (net (code "76") (name "unconnected-(U1-PadDEC4)") (class "Default")
      (node (ref "U1") (pin "DEC4") (pinfunction "DEC4_DEC4") (pintype "bidirectional"))
    )
    (net (code "77") (name "unconnected-(U1-PadRESET)") (class "Default")
      (node (ref "U1") (pin "RESET") (pinfunction "RESET_RESET") (pintype "bidirectional"))
    )
    (net (code "78") (name "unconnected-(U1-PadRTS)") (class "Default")
      (node (ref "U1") (pin "RTS") (pinfunction "RTS_RTS") (pintype "bidirectional"))
    )
    (net (code "79") (name "unconnected-(U2A-PA4-Pad14)") (class "Default")
      (node (ref "U2") (pin "14") (pinfunction "PA4_14") (pintype "bidirectional"))
    )
    (net (code "80") (name "unconnected-(U2A-PA15-Pad38)") (class "Default")
      (node (ref "U2") (pin "38") (pinfunction "PA15_38") (pintype "bidirectional"))
    )
    (net (code "81") (name "unconnected-(U2A-PB3-Pad39)") (class "Default")
      (node (ref "U2") (pin "39") (pinfunction "PB3_39") (pintype "bidirectional"))
    )
    (net (code "82") (name "unconnected-(U2A-PC13-Pad2)") (class "Default")
      (node (ref "U2") (pin "2") (pinfunction "PC13_2") (pintype "bidirectional"))
    )
    (net (code "83") (name "unconnected-(U2A-PC14-OSC32_IN-Pad3)") (class "Default")
      (node (ref "U2") (pin "3") (pinfunction "PC14-OSC32_IN_3") (pintype "bidirectional"))
    )
    (net (code "84") (name "unconnected-(U2A-PC15-OSC32_OUT-Pad4)") (class "Default")
      (node (ref "U2") (pin "4") (pinfunction "PC15-OSC32_OUT_4") (pintype "bidirectional"))
    )
    (net (code "85") (name "unconnected-(U14-Pad3V3)") (class "Default")
      (node (ref "U14") (pin "3V3") (pinfunction "3V3_3V3") (pintype "bidirectional"))
    )
    (net (code "86") (name "unconnected-(U14-PadPB0)") (class "Default")
      (node (ref "U14") (pin "PB0") (pinfunction "PB0_PB0") (pintype "bidirectional"))
    )
    (net (code "87") (name "unconnected-(U14-PadPB1)") (class "Default")
      (node (ref "U14") (pin "PB1") (pinfunction "PB1_PB1") (pintype "bidirectional"))
    )
    (net (code "88") (name "unconnected-(U14-PadPB3)") (class "Default")
      (node (ref "U14") (pin "PB3") (pinfunction "PB3_PB3") (pintype "bidirectional"))
    )
    (net (code "89") (name "unconnected-(U14-PadRST)") (class "Default")
      (node (ref "U14") (pin "RST") (pinfunction "RST_RST") (pintype "bidirectional"))
    )
    (net (code "90") (name "unconnected-(U14-PadSWIM)") (class "Default")
      (node (ref "U14") (pin "SWIM") (pinfunction "SWIM_SWIM") (pintype "bidirectional"))
    )
  )
)
